# AnemometerTHT.net
KiCad netlist of a schematic drawn in EAGLE
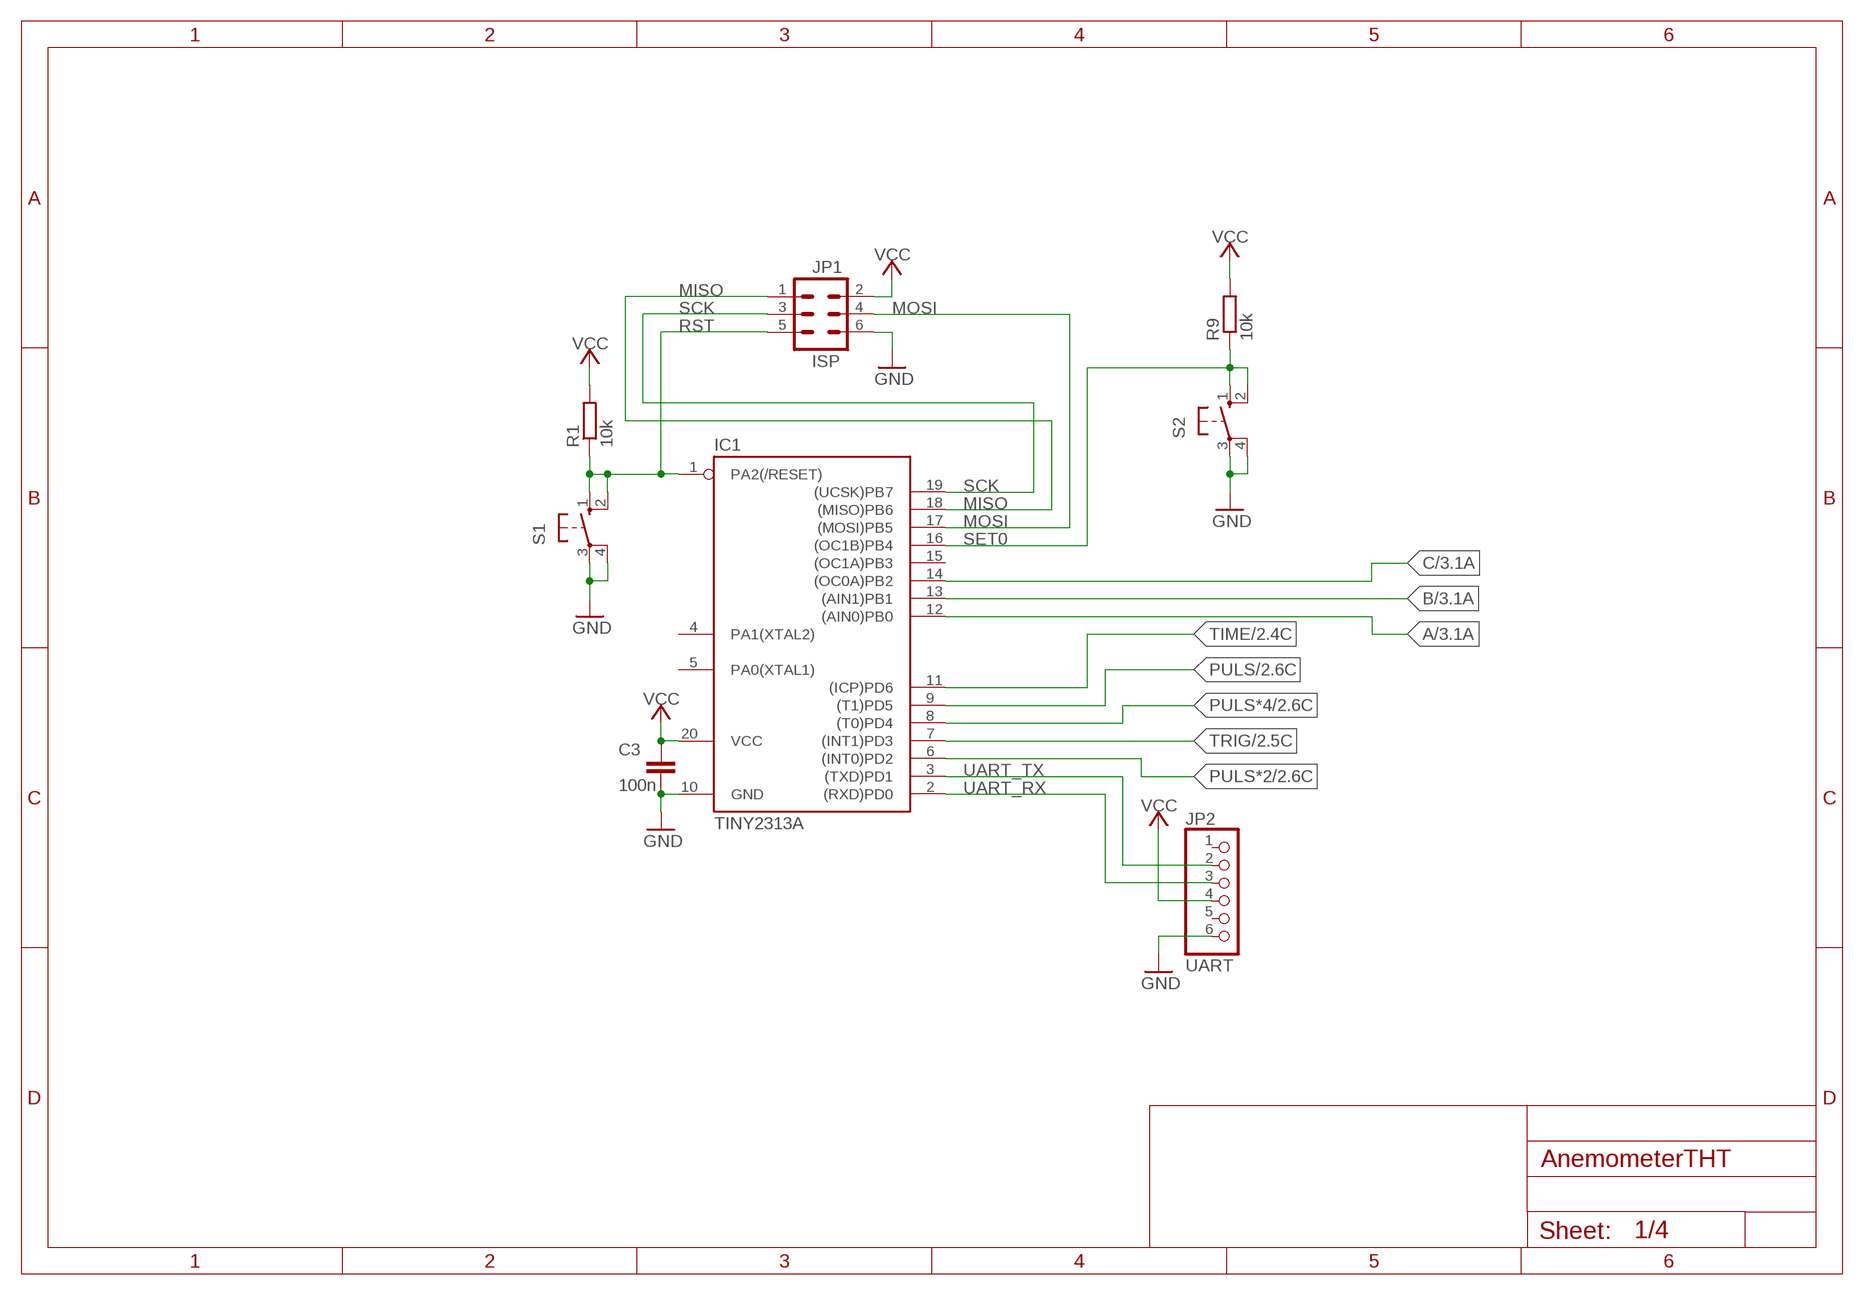
[diagram p0: schematic, sheet 1]
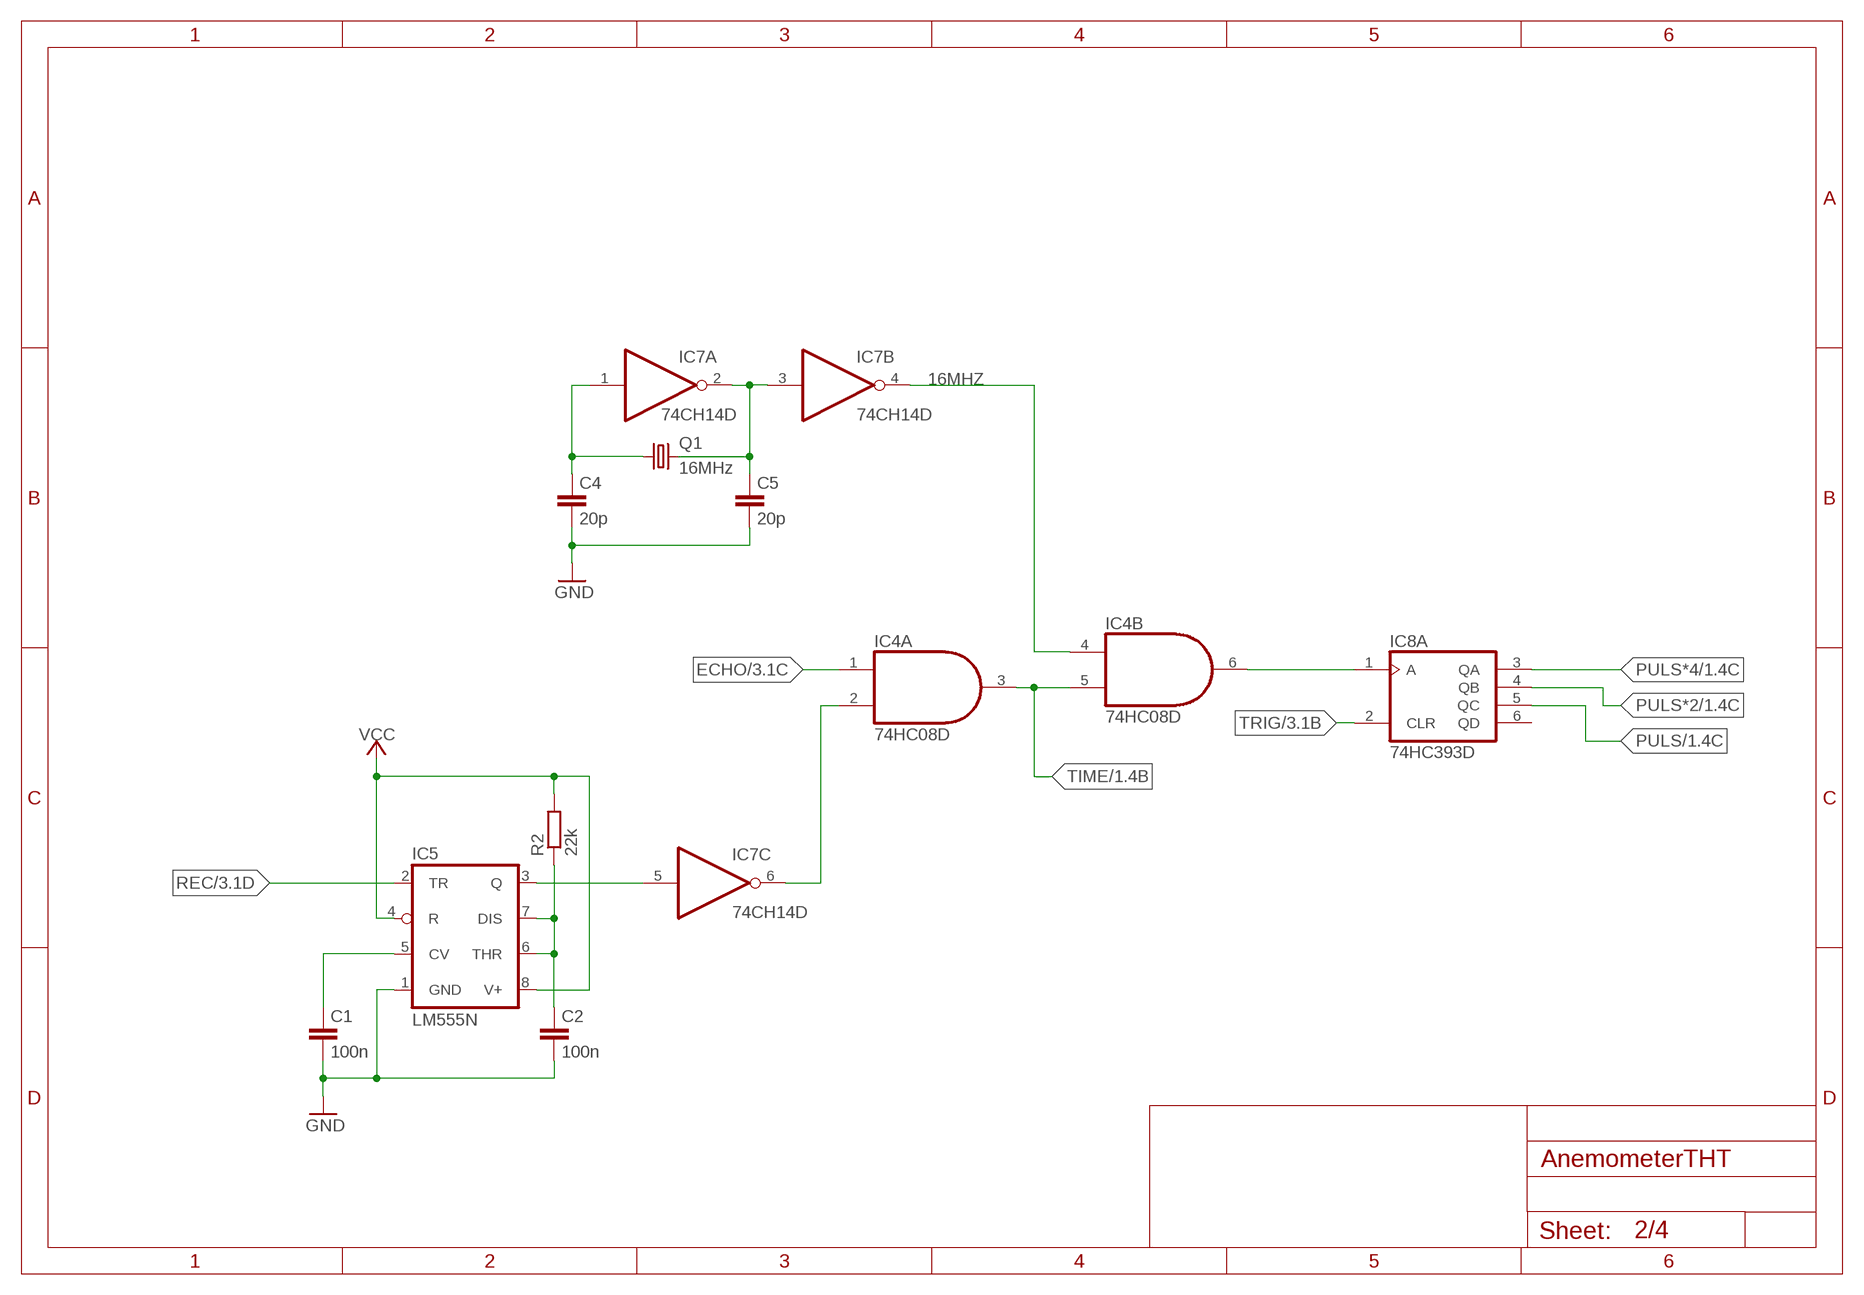
[diagram p1: schematic, sheet 2]
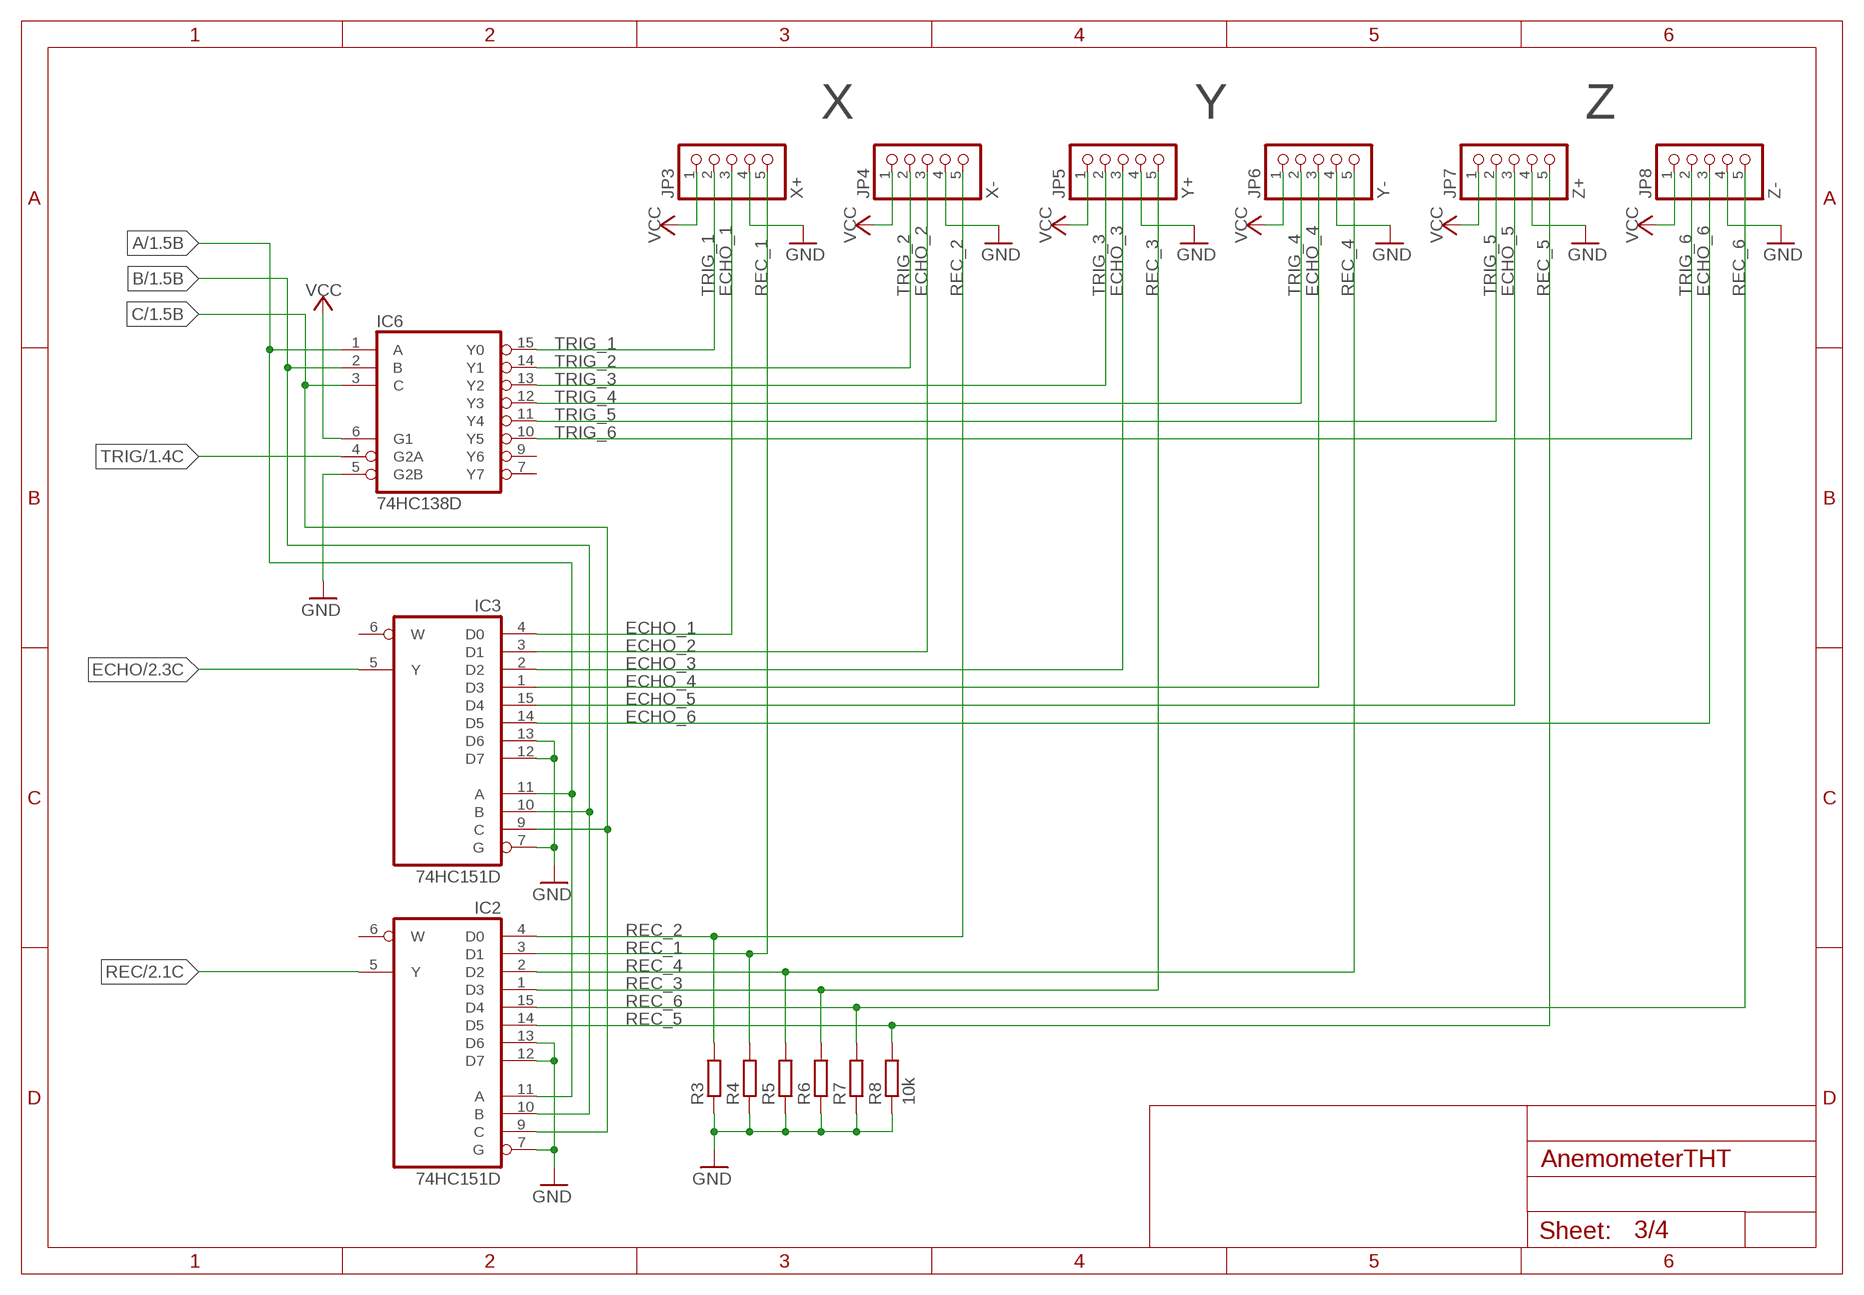
[diagram p2: schematic, sheet 3]
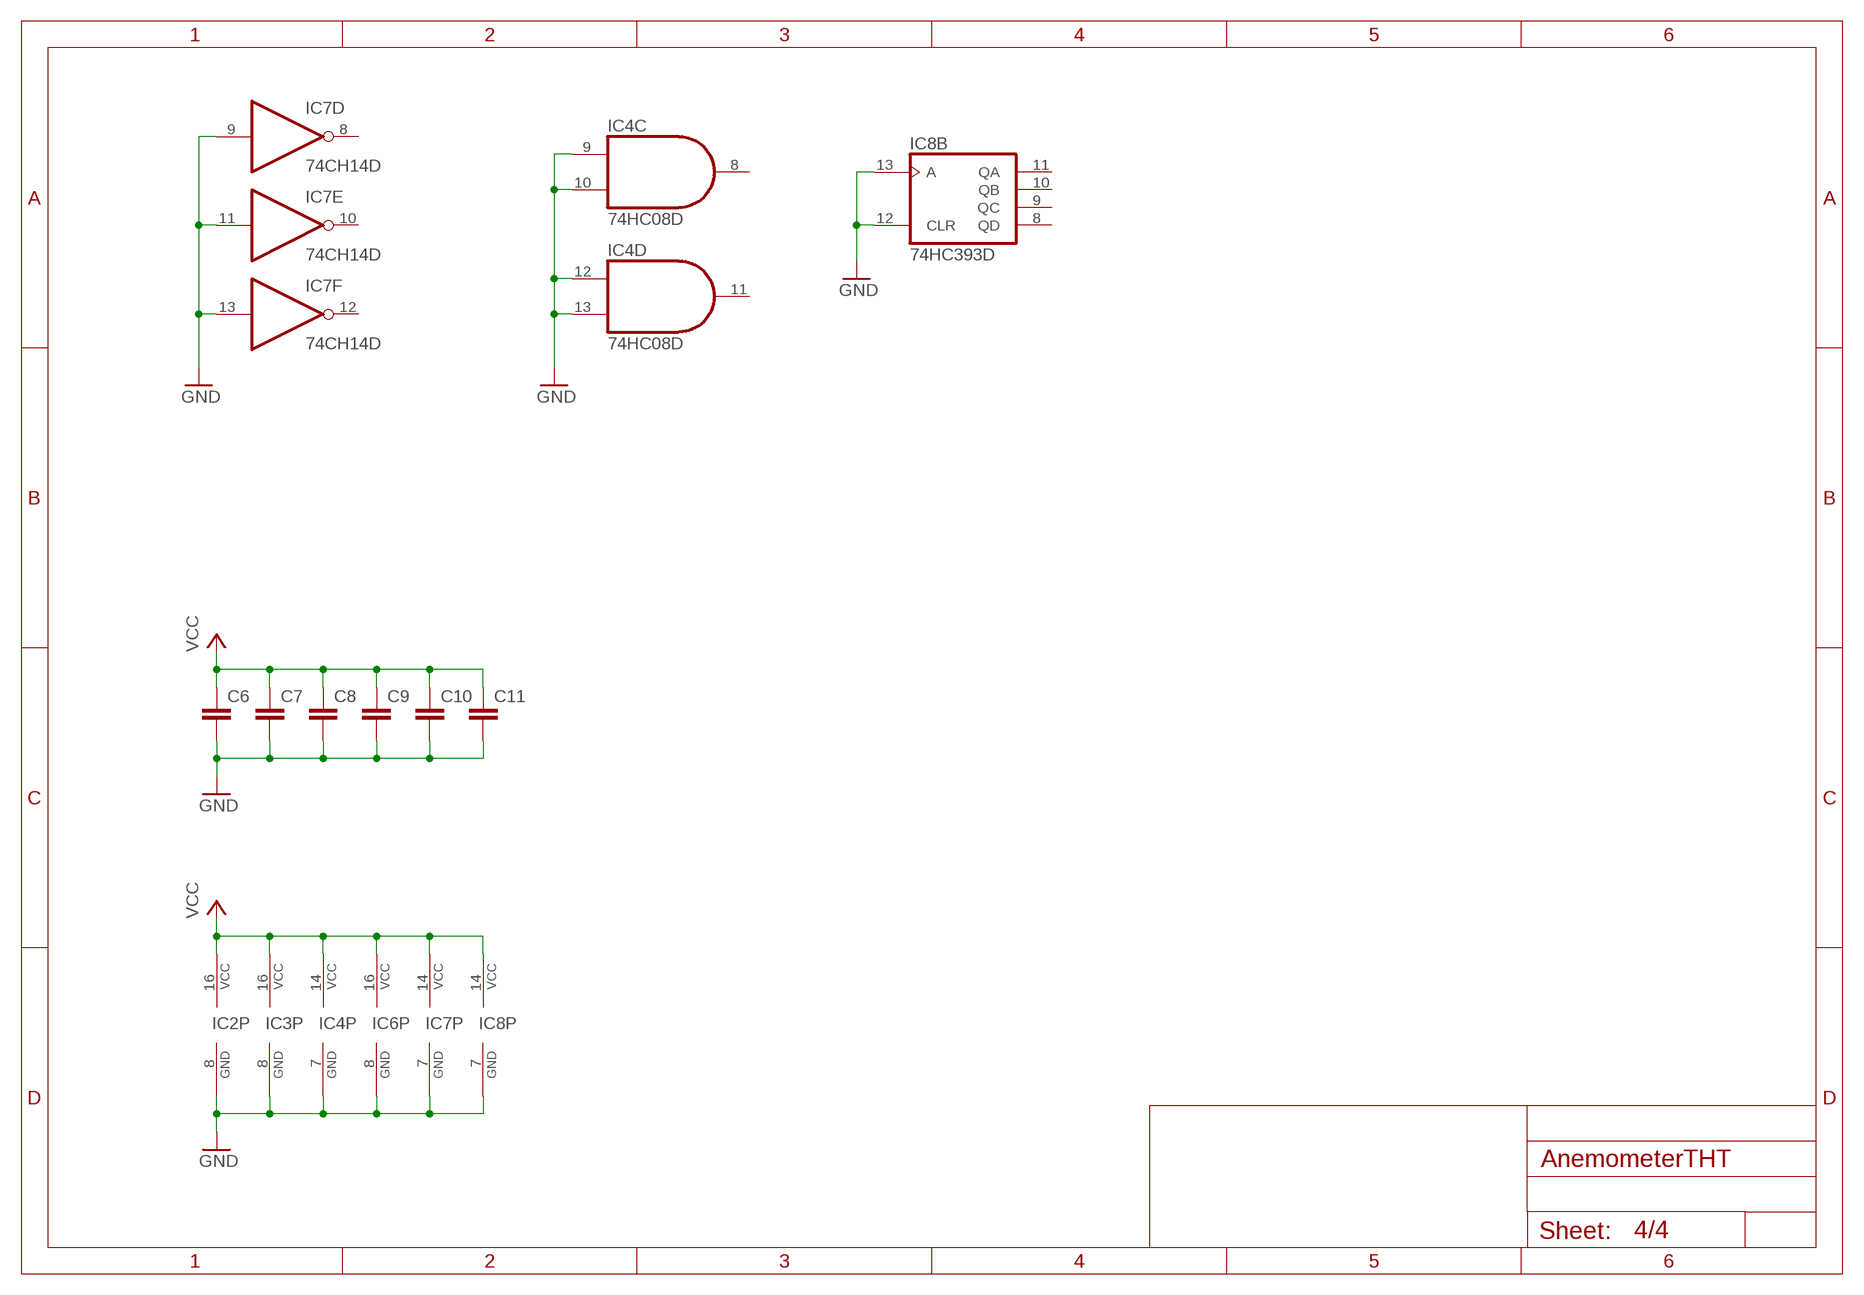
[diagram p3: schematic, sheet 4]

(export (version "E")
  (design (tool "Eeschema 10.0.6"))
  (components
    (comp (ref "IC2")
      (value "74HC151D")
      (footprint "eagle-import:DIL16")
      (libsource (lib "eagle-import") (part "74151NLS"))
    )
    (comp (ref "IC3")
      (value "74HC151D")
      (footprint "eagle-import:DIL16")
      (libsource (lib "eagle-import") (part "74151NLS"))
    )
    (comp (ref "IC6")
      (value "74HC138D")
      (footprint "eagle-import:DIL16")
      (libsource (lib "eagle-import") (part "74138NLS"))
    )
    (comp (ref "JP3")
      (value "X+")
      (footprint "eagle-import:1X05")
      (libsource (lib "eagle-import") (part "PINHD-1X5"))
    )
    (comp (ref "JP4")
      (value "X-")
      (footprint "eagle-import:1X05")
      (libsource (lib "eagle-import") (part "PINHD-1X5"))
    )
    (comp (ref "JP5")
      (value "Y+")
      (footprint "eagle-import:1X05")
      (libsource (lib "eagle-import") (part "PINHD-1X5"))
    )
    (comp (ref "JP6")
      (value "Y-")
      (footprint "eagle-import:1X05")
      (libsource (lib "eagle-import") (part "PINHD-1X5"))
    )
    (comp (ref "JP7")
      (value "Z+")
      (footprint "eagle-import:1X05")
      (libsource (lib "eagle-import") (part "PINHD-1X5"))
    )
    (comp (ref "JP8")
      (value "Z-")
      (footprint "eagle-import:1X05")
      (libsource (lib "eagle-import") (part "PINHD-1X5"))
    )
    (comp (ref "R3")
      (value "10k")
      (footprint "eagle-import:0204_7")
      (libsource (lib "eagle-import") (part "R-EU_0204/7"))
    )
    (comp (ref "R4")
      (value "10k")
      (footprint "eagle-import:0204_7")
      (libsource (lib "eagle-import") (part "R-EU_0204/7"))
    )
    (comp (ref "R5")
      (value "10k")
      (footprint "eagle-import:0204_7")
      (libsource (lib "eagle-import") (part "R-EU_0204/7"))
    )
    (comp (ref "R6")
      (value "10k")
      (footprint "eagle-import:0204_7")
      (libsource (lib "eagle-import") (part "R-EU_0204/7"))
    )
    (comp (ref "R7")
      (value "10k")
      (footprint "eagle-import:0204_7")
      (libsource (lib "eagle-import") (part "R-EU_0204/7"))
    )
    (comp (ref "R8")
      (value "10k")
      (footprint "eagle-import:0204_7")
      (libsource (lib "eagle-import") (part "R-EU_0204/7"))
    )
    (comp (ref "C6")
      (value "C-EU050-030X075")
      (footprint "eagle-import:C050-030X075")
      (libsource (lib "eagle-import") (part "C-EU050-030X075"))
    )
    (comp (ref "C7")
      (value "C-EU050-030X075")
      (footprint "eagle-import:C050-030X075")
      (libsource (lib "eagle-import") (part "C-EU050-030X075"))
    )
    (comp (ref "C8")
      (value "C-EU050-030X075")
      (footprint "eagle-import:C050-030X075")
      (libsource (lib "eagle-import") (part "C-EU050-030X075"))
    )
    (comp (ref "C9")
      (value "C-EU050-030X075")
      (footprint "eagle-import:C050-030X075")
      (libsource (lib "eagle-import") (part "C-EU050-030X075"))
    )
    (comp (ref "C10")
      (value "C-EU050-030X075")
      (footprint "eagle-import:C050-030X075")
      (libsource (lib "eagle-import") (part "C-EU050-030X075"))
    )
    (comp (ref "C11")
      (value "C-EU050-030X075")
      (footprint "eagle-import:C050-030X075")
      (libsource (lib "eagle-import") (part "C-EU050-030X075"))
    )
    (comp (ref "IC4")
      (value "74HC08D")
      (footprint "eagle-import:DIL14")
      (libsource (lib "eagle-import") (part "7408NALS"))
    )
    (comp (ref "IC7")
      (value "74CH14D")
      (footprint "eagle-import:DIL14")
      (libsource (lib "eagle-import") (part "7404NALS"))
    )
    (comp (ref "IC8")
      (value "74HC393D")
      (footprint "eagle-import:DIL14")
      (libsource (lib "eagle-import") (part "74393NLS"))
    )
    (comp (ref "C1")
      (value "100n")
      (footprint "eagle-import:C050-030X075")
      (libsource (lib "eagle-import") (part "C-EU050-030X075"))
    )
    (comp (ref "C2")
      (value "100n")
      (footprint "eagle-import:C050-030X075")
      (libsource (lib "eagle-import") (part "C-EU050-030X075"))
    )
    (comp (ref "C4")
      (value "20p")
      (footprint "eagle-import:C050-030X075")
      (libsource (lib "eagle-import") (part "C-EU050-030X075"))
    )
    (comp (ref "C5")
      (value "20p")
      (footprint "eagle-import:C050-030X075")
      (libsource (lib "eagle-import") (part "C-EU050-030X075"))
    )
    (comp (ref "IC5")
      (value "LM555N")
      (footprint "eagle-import:DIL08")
      (libsource (lib "eagle-import") (part "555NLM"))
    )
    (comp (ref "Q1")
      (value "16MHz")
      (footprint "eagle-import:HC49U70")
      (libsource (lib "eagle-import") (part "CRYSTALHC49U70"))
    )
    (comp (ref "R2")
      (value "22k")
      (footprint "eagle-import:0204_7")
      (libsource (lib "eagle-import") (part "R-EU_0204/7"))
    )
    (comp (ref "C3")
      (value "100n")
      (footprint "eagle-import:C050-030X075")
      (libsource (lib "eagle-import") (part "C-EU050-030X075"))
    )
    (comp (ref "IC1")
      (value "TINY2313A")
      (footprint "eagle-import:DIL20")
      (libsource (lib "eagle-import") (part "TINY2313-P"))
    )
    (comp (ref "JP1")
      (value "ISP")
      (footprint "eagle-import:ML6")
      (libsource (lib "eagle-import") (part "ML6"))
    )
    (comp (ref "JP2")
      (value "UART")
      (footprint "eagle-import:1X06")
      (libsource (lib "eagle-import") (part "PINHD-1X6"))
    )
    (comp (ref "R1")
      (value "10k")
      (footprint "eagle-import:0204_7")
      (libsource (lib "eagle-import") (part "R-EU_0204/7"))
    )
    (comp (ref "R9")
      (value "10k")
      (footprint "eagle-import:0204_7")
      (libsource (lib "eagle-import") (part "R-EU_0204/7"))
    )
    (comp (ref "S1")
      (value "10-XX")
      (footprint "eagle-import:B3F-10XX")
      (fields (field (name "MPN") "B3F-1000"))
      (libsource (lib "eagle-import") (part "10-XX"))
    )
    (comp (ref "S2")
      (value "10-XX")
      (footprint "eagle-import:B3F-10XX")
      (fields (field (name "MPN") "B3F-1000"))
      (libsource (lib "eagle-import") (part "10-XX"))
    )
  )
  (nets
    (net (code "1") (name "16MHZ") (class "Default")
      (node (ref "IC4") (pin "4") (pinfunction "I0_4") (pintype "input"))
      (node (ref "IC7") (pin "4") (pinfunction "O_4") (pintype "output"))
    )
    (net (code "2") (name "A") (class "Default")
      (node (ref "IC1") (pin "12") (pinfunction "(AIN0)PB0_12") (pintype "bidirectional"))
      (node (ref "IC2") (pin "11") (pinfunction "A_11") (pintype "input"))
      (node (ref "IC3") (pin "11") (pinfunction "A_11") (pintype "input"))
      (node (ref "IC6") (pin "1") (pinfunction "A_1") (pintype "input"))
    )
    (net (code "3") (name "B") (class "Default")
      (node (ref "IC1") (pin "13") (pinfunction "(AIN1)PB1_13") (pintype "bidirectional"))
      (node (ref "IC2") (pin "10") (pinfunction "B_10") (pintype "input"))
      (node (ref "IC3") (pin "10") (pinfunction "B_10") (pintype "input"))
      (node (ref "IC6") (pin "2") (pinfunction "B_2") (pintype "input"))
    )
    (net (code "4") (name "C") (class "Default")
      (node (ref "IC1") (pin "14") (pinfunction "(OC0A)PB2_14") (pintype "bidirectional"))
      (node (ref "IC2") (pin "9") (pinfunction "C_9") (pintype "input"))
      (node (ref "IC3") (pin "9") (pinfunction "C_9") (pintype "input"))
      (node (ref "IC6") (pin "3") (pinfunction "C_3") (pintype "input"))
    )
    (net (code "5") (name "ECHO") (class "Default")
      (node (ref "IC3") (pin "5") (pinfunction "Y_5") (pintype "output"))
      (node (ref "IC4") (pin "1") (pinfunction "I0_1") (pintype "input"))
    )
    (net (code "6") (name "ECHO_1") (class "Default")
      (node (ref "IC3") (pin "4") (pinfunction "D0_4") (pintype "input"))
      (node (ref "JP3") (pin "3") (pinfunction "3_3") (pintype "passive"))
    )
    (net (code "7") (name "ECHO_2") (class "Default")
      (node (ref "IC3") (pin "3") (pinfunction "D1_3") (pintype "input"))
      (node (ref "JP4") (pin "3") (pinfunction "3_3") (pintype "passive"))
    )
    (net (code "8") (name "ECHO_3") (class "Default")
      (node (ref "IC3") (pin "2") (pinfunction "D2_2") (pintype "input"))
      (node (ref "JP5") (pin "3") (pinfunction "3_3") (pintype "passive"))
    )
    (net (code "9") (name "ECHO_4") (class "Default")
      (node (ref "IC3") (pin "1") (pinfunction "D3_1") (pintype "input"))
      (node (ref "JP6") (pin "3") (pinfunction "3_3") (pintype "passive"))
    )
    (net (code "10") (name "ECHO_5") (class "Default")
      (node (ref "IC3") (pin "15") (pinfunction "D4_15") (pintype "input"))
      (node (ref "JP7") (pin "3") (pinfunction "3_3") (pintype "passive"))
    )
    (net (code "11") (name "ECHO_6") (class "Default")
      (node (ref "IC3") (pin "14") (pinfunction "D5_14") (pintype "input"))
      (node (ref "JP8") (pin "3") (pinfunction "3_3") (pintype "passive"))
    )
    (net (code "12") (name "GND") (class "Default")
      (node (ref "C1") (pin "2") (pinfunction "2_2") (pintype "passive"))
      (node (ref "C10") (pin "2") (pinfunction "2_2") (pintype "passive"))
      (node (ref "C11") (pin "2") (pinfunction "2_2") (pintype "passive"))
      (node (ref "C2") (pin "2") (pinfunction "2_2") (pintype "passive"))
      (node (ref "C3") (pin "2") (pinfunction "2_2") (pintype "passive"))
      (node (ref "C4") (pin "2") (pinfunction "2_2") (pintype "passive"))
      (node (ref "C5") (pin "2") (pinfunction "2_2") (pintype "passive"))
      (node (ref "C6") (pin "2") (pinfunction "2_2") (pintype "passive"))
      (node (ref "C7") (pin "2") (pinfunction "2_2") (pintype "passive"))
      (node (ref "C8") (pin "2") (pinfunction "2_2") (pintype "passive"))
      (node (ref "C9") (pin "2") (pinfunction "2_2") (pintype "passive"))
      (node (ref "IC1") (pin "10") (pinfunction "GND_10") (pintype "power_in"))
      (node (ref "IC2") (pin "12") (pinfunction "D7_12") (pintype "input"))
      (node (ref "IC2") (pin "13") (pinfunction "D6_13") (pintype "input"))
      (node (ref "IC2") (pin "7") (pinfunction "G_7") (pintype "input"))
      (node (ref "IC2") (pin "8") (pinfunction "GND_8") (pintype "power_in"))
      (node (ref "IC3") (pin "12") (pinfunction "D7_12") (pintype "input"))
      (node (ref "IC3") (pin "13") (pinfunction "D6_13") (pintype "input"))
      (node (ref "IC3") (pin "7") (pinfunction "G_7") (pintype "input"))
      (node (ref "IC3") (pin "8") (pinfunction "GND_8") (pintype "power_in"))
      (node (ref "IC4") (pin "10") (pinfunction "I1_10") (pintype "input"))
      (node (ref "IC4") (pin "12") (pinfunction "I0_12") (pintype "input"))
      (node (ref "IC4") (pin "13") (pinfunction "I1_13") (pintype "input"))
      (node (ref "IC4") (pin "7") (pinfunction "GND_7") (pintype "power_in"))
      (node (ref "IC4") (pin "9") (pinfunction "I0_9") (pintype "input"))
      (node (ref "IC5") (pin "1") (pinfunction "GND_1") (pintype "power_in"))
      (node (ref "IC6") (pin "5") (pinfunction "G2B_5") (pintype "input"))
      (node (ref "IC6") (pin "8") (pinfunction "GND_8") (pintype "power_in"))
      (node (ref "IC7") (pin "11") (pinfunction "I_11") (pintype "input"))
      (node (ref "IC7") (pin "13") (pinfunction "I_13") (pintype "input"))
      (node (ref "IC7") (pin "7") (pinfunction "GND_7") (pintype "power_in"))
      (node (ref "IC7") (pin "9") (pinfunction "I_9") (pintype "input"))
      (node (ref "IC8") (pin "12") (pinfunction "CLR_12") (pintype "input"))
      (node (ref "IC8") (pin "13") (pinfunction "A_13") (pintype "input"))
      (node (ref "IC8") (pin "7") (pinfunction "GND_7") (pintype "power_in"))
      (node (ref "JP1") (pin "6") (pinfunction "6_6") (pintype "passive"))
      (node (ref "JP2") (pin "6") (pinfunction "6_6") (pintype "passive"))
      (node (ref "JP3") (pin "4") (pinfunction "4_4") (pintype "passive"))
      (node (ref "JP4") (pin "4") (pinfunction "4_4") (pintype "passive"))
      (node (ref "JP5") (pin "4") (pinfunction "4_4") (pintype "passive"))
      (node (ref "JP6") (pin "4") (pinfunction "4_4") (pintype "passive"))
      (node (ref "JP7") (pin "4") (pinfunction "4_4") (pintype "passive"))
      (node (ref "JP8") (pin "4") (pinfunction "4_4") (pintype "passive"))
      (node (ref "R3") (pin "1") (pinfunction "1_1") (pintype "passive"))
      (node (ref "R4") (pin "1") (pinfunction "1_1") (pintype "passive"))
      (node (ref "R5") (pin "1") (pinfunction "1_1") (pintype "passive"))
      (node (ref "R6") (pin "1") (pinfunction "1_1") (pintype "passive"))
      (node (ref "R7") (pin "1") (pinfunction "1_1") (pintype "passive"))
      (node (ref "R8") (pin "1") (pinfunction "1_1") (pintype "passive"))
      (node (ref "S1") (pin "3") (pinfunction "P_3") (pintype "passive"))
      (node (ref "S1") (pin "4") (pinfunction "P1_4") (pintype "passive"))
      (node (ref "S2") (pin "3") (pinfunction "P_3") (pintype "passive"))
      (node (ref "S2") (pin "4") (pinfunction "P1_4") (pintype "passive"))
    )
    (net (code "13") (name "MISO") (class "Default")
      (node (ref "IC1") (pin "18") (pinfunction "(MISO)PB6_18") (pintype "bidirectional"))
      (node (ref "JP1") (pin "1") (pinfunction "1_1") (pintype "passive"))
    )
    (net (code "14") (name "MOSI") (class "Default")
      (node (ref "IC1") (pin "17") (pinfunction "(MOSI)PB5_17") (pintype "bidirectional"))
      (node (ref "JP1") (pin "4") (pinfunction "4_4") (pintype "passive"))
    )
    (net (code "15") (name "Net-(IC4A-I1)") (class "Default")
      (node (ref "IC4") (pin "2") (pinfunction "I1_2") (pintype "input"))
      (node (ref "IC7") (pin "6") (pinfunction "O_6") (pintype "output"))
    )
    (net (code "16") (name "Net-(IC4B-O)") (class "Default")
      (node (ref "IC4") (pin "6") (pinfunction "O_6") (pintype "output"))
      (node (ref "IC8") (pin "1") (pinfunction "A_1") (pintype "input"))
    )
    (net (code "17") (name "Net-(IC5-CV)") (class "Default")
      (node (ref "C1") (pin "1") (pinfunction "1_1") (pintype "passive"))
      (node (ref "IC5") (pin "5") (pinfunction "CV_5") (pintype "input"))
    )
    (net (code "18") (name "Net-(IC5-DIS)") (class "Default")
      (node (ref "C2") (pin "1") (pinfunction "1_1") (pintype "passive"))
      (node (ref "IC5") (pin "6") (pinfunction "THR_6") (pintype "input"))
      (node (ref "IC5") (pin "7") (pinfunction "DIS_7") (pintype "input"))
      (node (ref "R2") (pin "1") (pinfunction "1_1") (pintype "passive"))
    )
    (net (code "19") (name "Net-(IC5-Q)") (class "Default")
      (node (ref "IC5") (pin "3") (pinfunction "Q_3") (pintype "output"))
      (node (ref "IC7") (pin "5") (pinfunction "I_5") (pintype "input"))
    )
    (net (code "20") (name "Net-(IC7A-I)") (class "Default")
      (node (ref "C4") (pin "1") (pinfunction "1_1") (pintype "passive"))
      (node (ref "IC7") (pin "1") (pinfunction "I_1") (pintype "input"))
      (node (ref "Q1") (pin "1") (pinfunction "1_1") (pintype "passive"))
    )
    (net (code "21") (name "Net-(IC7A-O)") (class "Default")
      (node (ref "C5") (pin "1") (pinfunction "1_1") (pintype "passive"))
      (node (ref "IC7") (pin "2") (pinfunction "O_2") (pintype "output"))
      (node (ref "IC7") (pin "3") (pinfunction "I_3") (pintype "input"))
      (node (ref "Q1") (pin "2") (pinfunction "2_2") (pintype "passive"))
    )
    (net (code "22") (name "PULS") (class "Default")
      (node (ref "IC1") (pin "9") (pinfunction "(T1)PD5_9") (pintype "bidirectional"))
      (node (ref "IC8") (pin "5") (pinfunction "QC_5") (pintype "output"))
    )
    (net (code "23") (name "PULS*2") (class "Default")
      (node (ref "IC1") (pin "6") (pinfunction "(INT0)PD2_6") (pintype "bidirectional"))
      (node (ref "IC8") (pin "4") (pinfunction "QB_4") (pintype "output"))
    )
    (net (code "24") (name "PULS*4") (class "Default")
      (node (ref "IC1") (pin "8") (pinfunction "(T0)PD4_8") (pintype "bidirectional"))
      (node (ref "IC8") (pin "3") (pinfunction "QA_3") (pintype "output"))
    )
    (net (code "25") (name "REC") (class "Default")
      (node (ref "IC2") (pin "5") (pinfunction "Y_5") (pintype "output"))
      (node (ref "IC5") (pin "2") (pinfunction "TR_2") (pintype "input"))
    )
    (net (code "26") (name "REC_1") (class "Default")
      (node (ref "IC2") (pin "3") (pinfunction "D1_3") (pintype "input"))
      (node (ref "JP3") (pin "5") (pinfunction "5_5") (pintype "passive"))
      (node (ref "R4") (pin "2") (pinfunction "2_2") (pintype "passive"))
    )
    (net (code "27") (name "REC_2") (class "Default")
      (node (ref "IC2") (pin "4") (pinfunction "D0_4") (pintype "input"))
      (node (ref "JP4") (pin "5") (pinfunction "5_5") (pintype "passive"))
      (node (ref "R3") (pin "2") (pinfunction "2_2") (pintype "passive"))
    )
    (net (code "28") (name "REC_3") (class "Default")
      (node (ref "IC2") (pin "1") (pinfunction "D3_1") (pintype "input"))
      (node (ref "JP5") (pin "5") (pinfunction "5_5") (pintype "passive"))
      (node (ref "R6") (pin "2") (pinfunction "2_2") (pintype "passive"))
    )
    (net (code "29") (name "REC_4") (class "Default")
      (node (ref "IC2") (pin "2") (pinfunction "D2_2") (pintype "input"))
      (node (ref "JP6") (pin "5") (pinfunction "5_5") (pintype "passive"))
      (node (ref "R5") (pin "2") (pinfunction "2_2") (pintype "passive"))
    )
    (net (code "30") (name "REC_5") (class "Default")
      (node (ref "IC2") (pin "14") (pinfunction "D5_14") (pintype "input"))
      (node (ref "JP7") (pin "5") (pinfunction "5_5") (pintype "passive"))
      (node (ref "R8") (pin "2") (pinfunction "2_2") (pintype "passive"))
    )
    (net (code "31") (name "REC_6") (class "Default")
      (node (ref "IC2") (pin "15") (pinfunction "D4_15") (pintype "input"))
      (node (ref "JP8") (pin "5") (pinfunction "5_5") (pintype "passive"))
      (node (ref "R7") (pin "2") (pinfunction "2_2") (pintype "passive"))
    )
    (net (code "32") (name "RST") (class "Default")
      (node (ref "IC1") (pin "1") (pinfunction "PA2(/RESET)_1") (pintype "input"))
      (node (ref "JP1") (pin "5") (pinfunction "5_5") (pintype "passive"))
      (node (ref "R1") (pin "1") (pinfunction "1_1") (pintype "passive"))
      (node (ref "S1") (pin "1") (pinfunction "S_1") (pintype "passive"))
      (node (ref "S1") (pin "2") (pinfunction "S1_2") (pintype "passive"))
    )
    (net (code "33") (name "SCK") (class "Default")
      (node (ref "IC1") (pin "19") (pinfunction "(UCSK)PB7_19") (pintype "bidirectional"))
      (node (ref "JP1") (pin "3") (pinfunction "3_3") (pintype "passive"))
    )
    (net (code "34") (name "SET0") (class "Default")
      (node (ref "IC1") (pin "16") (pinfunction "(OC1B)PB4_16") (pintype "bidirectional"))
      (node (ref "R9") (pin "1") (pinfunction "1_1") (pintype "passive"))
      (node (ref "S2") (pin "1") (pinfunction "S_1") (pintype "passive"))
      (node (ref "S2") (pin "2") (pinfunction "S1_2") (pintype "passive"))
    )
    (net (code "35") (name "TIME") (class "Default")
      (node (ref "IC1") (pin "11") (pinfunction "(ICP)PD6_11") (pintype "bidirectional"))
      (node (ref "IC4") (pin "3") (pinfunction "O_3") (pintype "output"))
      (node (ref "IC4") (pin "5") (pinfunction "I1_5") (pintype "input"))
    )
    (net (code "36") (name "TRIG") (class "Default")
      (node (ref "IC1") (pin "7") (pinfunction "(INT1)PD3_7") (pintype "bidirectional"))
      (node (ref "IC6") (pin "4") (pinfunction "G2A_4") (pintype "input"))
      (node (ref "IC8") (pin "2") (pinfunction "CLR_2") (pintype "input"))
    )
    (net (code "37") (name "TRIG_1") (class "Default")
      (node (ref "IC6") (pin "15") (pinfunction "Y0_15") (pintype "output"))
      (node (ref "JP3") (pin "2") (pinfunction "2_2") (pintype "passive"))
    )
    (net (code "38") (name "TRIG_2") (class "Default")
      (node (ref "IC6") (pin "14") (pinfunction "Y1_14") (pintype "output"))
      (node (ref "JP4") (pin "2") (pinfunction "2_2") (pintype "passive"))
    )
    (net (code "39") (name "TRIG_3") (class "Default")
      (node (ref "IC6") (pin "13") (pinfunction "Y2_13") (pintype "output"))
      (node (ref "JP5") (pin "2") (pinfunction "2_2") (pintype "passive"))
    )
    (net (code "40") (name "TRIG_4") (class "Default")
      (node (ref "IC6") (pin "12") (pinfunction "Y3_12") (pintype "output"))
      (node (ref "JP6") (pin "2") (pinfunction "2_2") (pintype "passive"))
    )
    (net (code "41") (name "TRIG_5") (class "Default")
      (node (ref "IC6") (pin "11") (pinfunction "Y4_11") (pintype "output"))
      (node (ref "JP7") (pin "2") (pinfunction "2_2") (pintype "passive"))
    )
    (net (code "42") (name "TRIG_6") (class "Default")
      (node (ref "IC6") (pin "10") (pinfunction "Y5_10") (pintype "output"))
      (node (ref "JP8") (pin "2") (pinfunction "2_2") (pintype "passive"))
    )
    (net (code "43") (name "UART_RX") (class "Default")
      (node (ref "IC1") (pin "2") (pinfunction "(RXD)PD0_2") (pintype "bidirectional"))
      (node (ref "JP2") (pin "3") (pinfunction "3_3") (pintype "passive"))
    )
    (net (code "44") (name "UART_TX") (class "Default")
      (node (ref "IC1") (pin "3") (pinfunction "(TXD)PD1_3") (pintype "bidirectional"))
      (node (ref "JP2") (pin "2") (pinfunction "2_2") (pintype "passive"))
    )
    (net (code "45") (name "VCC") (class "Default")
      (node (ref "C10") (pin "1") (pinfunction "1_1") (pintype "passive"))
      (node (ref "C11") (pin "1") (pinfunction "1_1") (pintype "passive"))
      (node (ref "C3") (pin "1") (pinfunction "1_1") (pintype "passive"))
      (node (ref "C6") (pin "1") (pinfunction "1_1") (pintype "passive"))
      (node (ref "C7") (pin "1") (pinfunction "1_1") (pintype "passive"))
      (node (ref "C8") (pin "1") (pinfunction "1_1") (pintype "passive"))
      (node (ref "C9") (pin "1") (pinfunction "1_1") (pintype "passive"))
      (node (ref "IC1") (pin "20") (pinfunction "VCC_20") (pintype "power_in"))
      (node (ref "IC2") (pin "16") (pinfunction "VCC_16") (pintype "power_in"))
      (node (ref "IC3") (pin "16") (pinfunction "VCC_16") (pintype "power_in"))
      (node (ref "IC4") (pin "14") (pinfunction "VCC_14") (pintype "power_in"))
      (node (ref "IC5") (pin "4") (pinfunction "R_4") (pintype "input"))
      (node (ref "IC5") (pin "8") (pinfunction "V+_8") (pintype "power_in"))
      (node (ref "IC6") (pin "16") (pinfunction "VCC_16") (pintype "power_in"))
      (node (ref "IC6") (pin "6") (pinfunction "G1_6") (pintype "input"))
      (node (ref "IC7") (pin "14") (pinfunction "VCC_14") (pintype "power_in"))
      (node (ref "IC8") (pin "14") (pinfunction "VCC_14") (pintype "power_in"))
      (node (ref "JP1") (pin "2") (pinfunction "2_2") (pintype "passive"))
      (node (ref "JP2") (pin "4") (pinfunction "4_4") (pintype "passive"))
      (node (ref "JP3") (pin "1") (pinfunction "1_1") (pintype "passive"))
      (node (ref "JP4") (pin "1") (pinfunction "1_1") (pintype "passive"))
      (node (ref "JP5") (pin "1") (pinfunction "1_1") (pintype "passive"))
      (node (ref "JP6") (pin "1") (pinfunction "1_1") (pintype "passive"))
      (node (ref "JP7") (pin "1") (pinfunction "1_1") (pintype "passive"))
      (node (ref "JP8") (pin "1") (pinfunction "1_1") (pintype "passive"))
      (node (ref "R1") (pin "2") (pinfunction "2_2") (pintype "passive"))
      (node (ref "R2") (pin "2") (pinfunction "2_2") (pintype "passive"))
      (node (ref "R9") (pin "2") (pinfunction "2_2") (pintype "passive"))
    )
    (net (code "46") (name "unconnected-(IC1-(OC1A)PB3-Pad15)") (class "Default")
      (node (ref "IC1") (pin "15") (pinfunction "(OC1A)PB3_15") (pintype "bidirectional"))
    )
    (net (code "47") (name "unconnected-(IC1-PA0(XTAL1)-Pad5)") (class "Default")
      (node (ref "IC1") (pin "5") (pinfunction "PA0(XTAL1)_5") (pintype "bidirectional"))
    )
    (net (code "48") (name "unconnected-(IC1-PA1(XTAL2)-Pad4)") (class "Default")
      (node (ref "IC1") (pin "4") (pinfunction "PA1(XTAL2)_4") (pintype "bidirectional"))
    )
    (net (code "49") (name "unconnected-(IC2A-W-Pad6)") (class "Default")
      (node (ref "IC2") (pin "6") (pinfunction "W_6") (pintype "output"))
    )
    (net (code "50") (name "unconnected-(IC3A-W-Pad6)") (class "Default")
      (node (ref "IC3") (pin "6") (pinfunction "W_6") (pintype "output"))
    )
    (net (code "51") (name "unconnected-(IC4C-O-Pad8)") (class "Default")
      (node (ref "IC4") (pin "8") (pinfunction "O_8") (pintype "output"))
    )
    (net (code "52") (name "unconnected-(IC4D-O-Pad11)") (class "Default")
      (node (ref "IC4") (pin "11") (pinfunction "O_11") (pintype "output"))
    )
    (net (code "53") (name "unconnected-(IC6A-Y6-Pad9)") (class "Default")
      (node (ref "IC6") (pin "9") (pinfunction "Y6_9") (pintype "output"))
    )
    (net (code "54") (name "unconnected-(IC6A-Y7-Pad7)") (class "Default")
      (node (ref "IC6") (pin "7") (pinfunction "Y7_7") (pintype "output"))
    )
    (net (code "55") (name "unconnected-(IC7D-O-Pad8)") (class "Default")
      (node (ref "IC7") (pin "8") (pinfunction "O_8") (pintype "output"))
    )
    (net (code "56") (name "unconnected-(IC7E-O-Pad10)") (class "Default")
      (node (ref "IC7") (pin "10") (pinfunction "O_10") (pintype "output"))
    )
    (net (code "57") (name "unconnected-(IC7F-O-Pad12)") (class "Default")
      (node (ref "IC7") (pin "12") (pinfunction "O_12") (pintype "output"))
    )
    (net (code "58") (name "unconnected-(IC8A-QD-Pad6)") (class "Default")
      (node (ref "IC8") (pin "6") (pinfunction "QD_6") (pintype "output"))
    )
    (net (code "59") (name "unconnected-(IC8B-QA-Pad11)") (class "Default")
      (node (ref "IC8") (pin "11") (pinfunction "QA_11") (pintype "output"))
    )
    (net (code "60") (name "unconnected-(IC8B-QB-Pad10)") (class "Default")
      (node (ref "IC8") (pin "10") (pinfunction "QB_10") (pintype "output"))
    )
    (net (code "61") (name "unconnected-(IC8B-QC-Pad9)") (class "Default")
      (node (ref "IC8") (pin "9") (pinfunction "QC_9") (pintype "output"))
    )
    (net (code "62") (name "unconnected-(IC8B-QD-Pad8)") (class "Default")
      (node (ref "IC8") (pin "8") (pinfunction "QD_8") (pintype "output"))
    )
    (net (code "63") (name "unconnected-(JP2-Pad1)") (class "Default")
      (node (ref "JP2") (pin "1") (pinfunction "1_1") (pintype "passive"))
    )
    (net (code "64") (name "unconnected-(JP2-Pad5)") (class "Default")
      (node (ref "JP2") (pin "5") (pinfunction "5_5") (pintype "passive"))
    )
  )
)
